# QBW01.net
KiCad netlist of a schematic drawn in Altium Designer
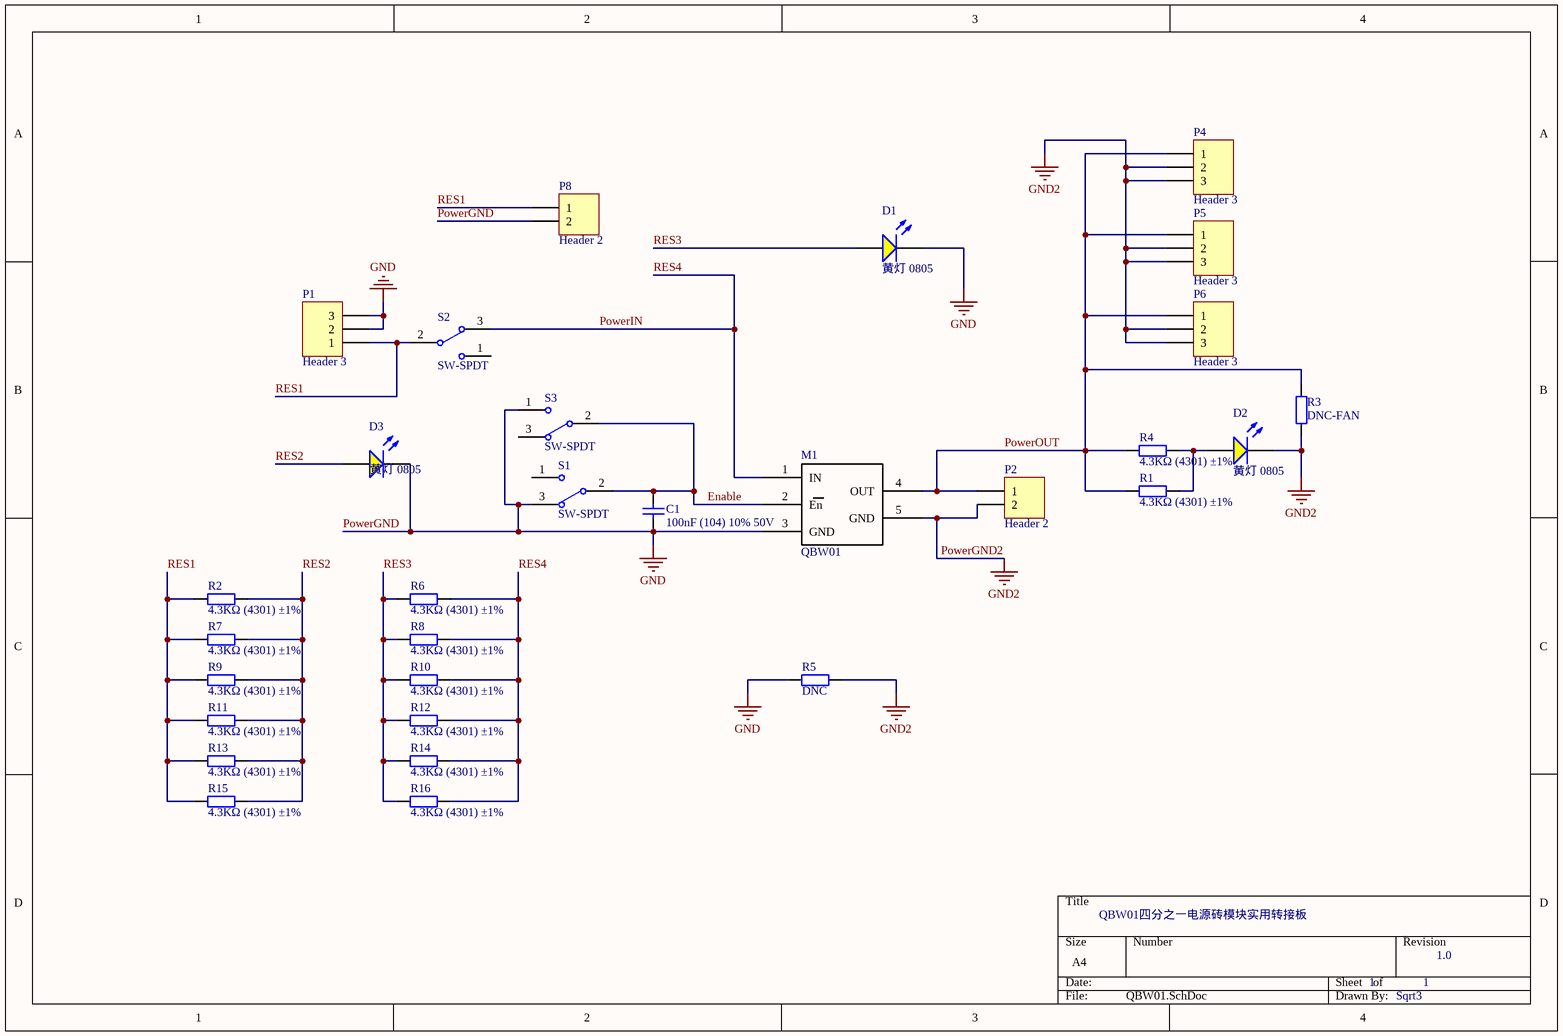
[diagram p0: QBW01.SchDoc]

(export (version "E")
  (design (tool "Eeschema 10.0.6"))
  (components
    (comp (ref "C1")
      (value "100nF (104) 10% 50V")
      (footprint "0603_C")
      (description "贴片电容")
      (libsource (lib "Miscellaneous Devices LC") (part "0603 100nF (104) 10% 50V"))
    )
    (comp (ref "D1")
      (value "黄灯 0805")
      (footprint "0805_LED_S1")
      (description "发光二极管")
      (libsource (lib "Miscellaneous Devices LC") (part "0805 黄灯"))
    )
    (comp (ref "D2")
      (value "黄灯 0805")
      (footprint "0805_LED_S1")
      (description "发光二极管")
      (libsource (lib "Miscellaneous Devices LC") (part "0805 黄灯"))
    )
    (comp (ref "D3")
      (value "黄灯 0805")
      (footprint "0805_LED_S1")
      (description "发光二极管")
      (libsource (lib "Miscellaneous Devices LC") (part "0805 黄灯"))
    )
    (comp (ref "M1") (value "QBW01") (footprint "QBW01") (libsource (lib "QBW01") (part "QBW01")))
    (comp (ref "P1")
      (value "Header 3")
      (footprint "PCBComponent_1")
      (description "Header, 3-Pin")
      (fields (field (name "PUBLISHER") "Altium Limited"))
      (libsource (lib "") (part "Header 3_1"))
    )
    (comp (ref "P2")
      (value "Header 2")
      (footprint "Header 1X2")
      (description "Header, 2-Pin")
      (fields (field (name "PUBLISHER") "Altium Limited"))
      (libsource (lib "Miscellaneous Connectors") (part "Header 2"))
    )
    (comp (ref "P4")
      (value "Header 3")
      (footprint "PCBComponent_1")
      (description "Header, 3-Pin")
      (fields (field (name "PUBLISHER") "Altium Limited"))
      (libsource (lib "Miscellaneous Connectors") (part "Header 3"))
    )
    (comp (ref "P5")
      (value "Header 3")
      (footprint "PCBComponent_1")
      (description "Header, 3-Pin")
      (fields (field (name "PUBLISHER") "Altium Limited"))
      (libsource (lib "Miscellaneous Connectors") (part "Header 3"))
    )
    (comp (ref "P6")
      (value "Header 3")
      (footprint "PCBComponent_1")
      (description "Header, 3-Pin")
      (fields (field (name "PUBLISHER") "Altium Limited"))
      (libsource (lib "Miscellaneous Connectors") (part "Header 3"))
    )
    (comp (ref "P8")
      (value "Header 2")
      (footprint "Header 1X2")
      (description "Header, 2-Pin")
      (fields (field (name "PUBLISHER") "Altium Limited"))
      (libsource (lib "Miscellaneous Connectors") (part "Header 2"))
    )
    (comp (ref "R1")
      (value "4.3KΩ (4301) ±1%")
      (footprint "0805_R")
      (description "贴片电阻")
      (libsource (lib "Miscellaneous Devices LC") (part "0805 4.3KΩ (4301) 1%"))
    )
    (comp (ref "R2")
      (value "4.3KΩ (4301) ±1%")
      (footprint "0805_R")
      (description "贴片电阻")
      (libsource (lib "Miscellaneous Devices LC") (part "0805 4.3KΩ (4301) 1%"))
    )
    (comp (ref "R3")
      (value "DNC-FAN")
      (footprint "1206_R")
      (description "贴片电阻")
      (libsource (lib "") (part "1206 1KΩ (1001) 1%_1"))
    )
    (comp (ref "R4")
      (value "4.3KΩ (4301) ±1%")
      (footprint "0805_R")
      (description "贴片电阻")
      (libsource (lib "Miscellaneous Devices LC") (part "0805 4.3KΩ (4301) 1%"))
    )
    (comp (ref "R5")
      (value "DNC")
      (footprint "1206_R")
      (description "贴片电阻")
      (libsource (lib "Miscellaneous Devices LC") (part "1206 1KΩ (1001) 1%"))
    )
    (comp (ref "R6")
      (value "4.3KΩ (4301) ±1%")
      (footprint "0805_R")
      (description "贴片电阻")
      (libsource (lib "Miscellaneous Devices LC") (part "0805 4.3KΩ (4301) 1%"))
    )
    (comp (ref "R7")
      (value "4.3KΩ (4301) ±1%")
      (footprint "0805_R")
      (description "贴片电阻")
      (libsource (lib "Miscellaneous Devices LC") (part "0805 4.3KΩ (4301) 1%"))
    )
    (comp (ref "R8")
      (value "4.3KΩ (4301) ±1%")
      (footprint "0805_R")
      (description "贴片电阻")
      (libsource (lib "Miscellaneous Devices LC") (part "0805 4.3KΩ (4301) 1%"))
    )
    (comp (ref "R9")
      (value "4.3KΩ (4301) ±1%")
      (footprint "0805_R")
      (description "贴片电阻")
      (libsource (lib "Miscellaneous Devices LC") (part "0805 4.3KΩ (4301) 1%"))
    )
    (comp (ref "R10")
      (value "4.3KΩ (4301) ±1%")
      (footprint "0805_R")
      (description "贴片电阻")
      (libsource (lib "Miscellaneous Devices LC") (part "0805 4.3KΩ (4301) 1%"))
    )
    (comp (ref "R11")
      (value "4.3KΩ (4301) ±1%")
      (footprint "0805_R")
      (description "贴片电阻")
      (libsource (lib "Miscellaneous Devices LC") (part "0805 4.3KΩ (4301) 1%"))
    )
    (comp (ref "R12")
      (value "4.3KΩ (4301) ±1%")
      (footprint "0805_R")
      (description "贴片电阻")
      (libsource (lib "Miscellaneous Devices LC") (part "0805 4.3KΩ (4301) 1%"))
    )
    (comp (ref "R13")
      (value "4.3KΩ (4301) ±1%")
      (footprint "0805_R")
      (description "贴片电阻")
      (libsource (lib "Miscellaneous Devices LC") (part "0805 4.3KΩ (4301) 1%"))
    )
    (comp (ref "R14")
      (value "4.3KΩ (4301) ±1%")
      (footprint "0805_R")
      (description "贴片电阻")
      (libsource (lib "Miscellaneous Devices LC") (part "0805 4.3KΩ (4301) 1%"))
    )
    (comp (ref "R15")
      (value "4.3KΩ (4301) ±1%")
      (footprint "0805_R")
      (description "贴片电阻")
      (libsource (lib "Miscellaneous Devices LC") (part "0805 4.3KΩ (4301) 1%"))
    )
    (comp (ref "R16")
      (value "4.3KΩ (4301) ±1%")
      (footprint "0805_R")
      (description "贴片电阻")
      (libsource (lib "Miscellaneous Devices LC") (part "0805 4.3KΩ (4301) 1%"))
    )
    (comp (ref "S1")
      (value "SW-SPDT")
      (footprint "SWITCH-SS12D07")
      (description "SPDT Subminiature Toggle Switch, Right Angle Mounting, Vertical Actuation")
      (fields (field (name "PUBLISHER") "Altium Limited"))
      (libsource (lib "Miscellaneous Devices") (part "SW-SPDT"))
    )
    (comp (ref "S2")
      (value "SW-SPDT")
      (footprint "SWITCH-YF")
      (description "SPDT Subminiature Toggle Switch, Right Angle Mounting, Vertical Actuation")
      (fields (field (name "PUBLISHER") "Altium Limited"))
      (libsource (lib "Miscellaneous Devices") (part "SW-SPDT"))
    )
    (comp (ref "S3")
      (value "SW-SPDT")
      (footprint "SWITCH-YF")
      (description "SPDT Subminiature Toggle Switch, Right Angle Mounting, Vertical Actuation")
      (fields (field (name "PUBLISHER") "Altium Limited"))
      (libsource (lib "Miscellaneous Devices") (part "SW-SPDT"))
    )
  )
  (nets
    (net (code "1") (name "/Enable") (class "Default")
      (node (ref "C1") (pin "2") (pinfunction "2_2") (pintype "passive"))
      (node (ref "M1") (pin "2") (pinfunction "En_2") (pintype "passive"))
      (node (ref "S1") (pin "2") (pinfunction "2_2") (pintype "passive"))
      (node (ref "S3") (pin "2") (pinfunction "2_2") (pintype "passive"))
    )
    (net (code "2") (name "/PowerIN") (class "Default")
      (node (ref "M1") (pin "1") (pinfunction "IN_1") (pintype "passive"))
      (node (ref "R10") (pin "2") (pinfunction "2_2") (pintype "passive"))
      (node (ref "R12") (pin "2") (pinfunction "2_2") (pintype "passive"))
      (node (ref "R14") (pin "2") (pinfunction "2_2") (pintype "passive"))
      (node (ref "R16") (pin "2") (pinfunction "2_2") (pintype "passive"))
      (node (ref "R6") (pin "2") (pinfunction "2_2") (pintype "passive"))
      (node (ref "R8") (pin "2") (pinfunction "2_2") (pintype "passive"))
      (node (ref "S2") (pin "3") (pinfunction "3_3") (pintype "passive"))
    )
    (net (code "3") (name "/PowerOUT") (class "Default")
      (node (ref "M1") (pin "4") (pinfunction "OUT_4") (pintype "passive"))
      (node (ref "P2") (pin "1") (pinfunction "1_1") (pintype "passive"))
      (node (ref "P4") (pin "1") (pinfunction "1_1") (pintype "passive"))
      (node (ref "P5") (pin "1") (pinfunction "1_1") (pintype "passive"))
      (node (ref "P6") (pin "1") (pinfunction "1_1") (pintype "passive"))
      (node (ref "R1") (pin "1") (pinfunction "1_1") (pintype "passive"))
      (node (ref "R3") (pin "2") (pinfunction "2_2") (pintype "passive"))
      (node (ref "R4") (pin "1") (pinfunction "1_1") (pintype "passive"))
    )
    (net (code "4") (name "/RES1") (class "Default")
      (node (ref "P1") (pin "1") (pinfunction "1_1") (pintype "passive"))
      (node (ref "P8") (pin "1") (pinfunction "1_1") (pintype "passive"))
      (node (ref "R11") (pin "1") (pinfunction "1_1") (pintype "passive"))
      (node (ref "R13") (pin "1") (pinfunction "1_1") (pintype "passive"))
      (node (ref "R15") (pin "1") (pinfunction "1_1") (pintype "passive"))
      (node (ref "R2") (pin "1") (pinfunction "1_1") (pintype "passive"))
      (node (ref "R7") (pin "1") (pinfunction "1_1") (pintype "passive"))
      (node (ref "R9") (pin "1") (pinfunction "1_1") (pintype "passive"))
      (node (ref "S2") (pin "2") (pinfunction "2_2") (pintype "passive"))
    )
    (net (code "5") (name "/RES2") (class "Default")
      (node (ref "D3") (pin "A") (pinfunction "A_A") (pintype "passive"))
      (node (ref "R11") (pin "2") (pinfunction "2_2") (pintype "passive"))
      (node (ref "R13") (pin "2") (pinfunction "2_2") (pintype "passive"))
      (node (ref "R15") (pin "2") (pinfunction "2_2") (pintype "passive"))
      (node (ref "R2") (pin "2") (pinfunction "2_2") (pintype "passive"))
      (node (ref "R7") (pin "2") (pinfunction "2_2") (pintype "passive"))
      (node (ref "R9") (pin "2") (pinfunction "2_2") (pintype "passive"))
    )
    (net (code "6") (name "/RES3") (class "Default")
      (node (ref "D1") (pin "A") (pinfunction "A_A") (pintype "passive"))
      (node (ref "R10") (pin "1") (pinfunction "1_1") (pintype "passive"))
      (node (ref "R12") (pin "1") (pinfunction "1_1") (pintype "passive"))
      (node (ref "R14") (pin "1") (pinfunction "1_1") (pintype "passive"))
      (node (ref "R16") (pin "1") (pinfunction "1_1") (pintype "passive"))
      (node (ref "R6") (pin "1") (pinfunction "1_1") (pintype "passive"))
      (node (ref "R8") (pin "1") (pinfunction "1_1") (pintype "passive"))
    )
    (net (code "7") (name "GND") (class "Default")
      (node (ref "C1") (pin "1") (pinfunction "1_1") (pintype "passive"))
      (node (ref "D1") (pin "K") (pinfunction "K_K") (pintype "passive"))
      (node (ref "D3") (pin "K") (pinfunction "K_K") (pintype "passive"))
      (node (ref "M1") (pin "3") (pinfunction "GND_3") (pintype "passive"))
      (node (ref "P1") (pin "2") (pinfunction "2_2") (pintype "passive"))
      (node (ref "P1") (pin "3") (pinfunction "3_3") (pintype "passive"))
      (node (ref "P8") (pin "2") (pinfunction "2_2") (pintype "passive"))
      (node (ref "R5") (pin "1") (pinfunction "1_1") (pintype "passive"))
      (node (ref "S1") (pin "3") (pinfunction "3_3") (pintype "passive"))
      (node (ref "S3") (pin "1") (pinfunction "1_1") (pintype "passive"))
    )
    (net (code "8") (name "GND2") (class "Default")
      (node (ref "D2") (pin "K") (pinfunction "K_K") (pintype "passive"))
      (node (ref "M1") (pin "5") (pinfunction "GND_5") (pintype "passive"))
      (node (ref "P2") (pin "2") (pinfunction "2_2") (pintype "passive"))
      (node (ref "P4") (pin "2") (pinfunction "2_2") (pintype "passive"))
      (node (ref "P4") (pin "3") (pinfunction "3_3") (pintype "passive"))
      (node (ref "P5") (pin "2") (pinfunction "2_2") (pintype "passive"))
      (node (ref "P5") (pin "3") (pinfunction "3_3") (pintype "passive"))
      (node (ref "P6") (pin "2") (pinfunction "2_2") (pintype "passive"))
      (node (ref "P6") (pin "3") (pinfunction "3_3") (pintype "passive"))
      (node (ref "R3") (pin "1") (pinfunction "1_1") (pintype "passive"))
      (node (ref "R5") (pin "2") (pinfunction "2_2") (pintype "passive"))
    )
    (net (code "9") (name "Net-(D2-PadA)") (class "Default")
      (node (ref "D2") (pin "A") (pinfunction "A_A") (pintype "passive"))
      (node (ref "R1") (pin "2") (pinfunction "2_2") (pintype "passive"))
      (node (ref "R4") (pin "2") (pinfunction "2_2") (pintype "passive"))
    )
    (net (code "10") (name "unconnected-(S1-Pad1)") (class "Default")
      (node (ref "S1") (pin "1") (pinfunction "1_1") (pintype "passive"))
    )
    (net (code "11") (name "unconnected-(S2-Pad1)") (class "Default")
      (node (ref "S2") (pin "1") (pinfunction "1_1") (pintype "passive"))
    )
    (net (code "12") (name "unconnected-(S3-Pad3)") (class "Default")
      (node (ref "S3") (pin "3") (pinfunction "3_3") (pintype "passive"))
    )
  )
)
